# ProgramableResistor.net
KiCad netlist of a schematic drawn in Altium Designer
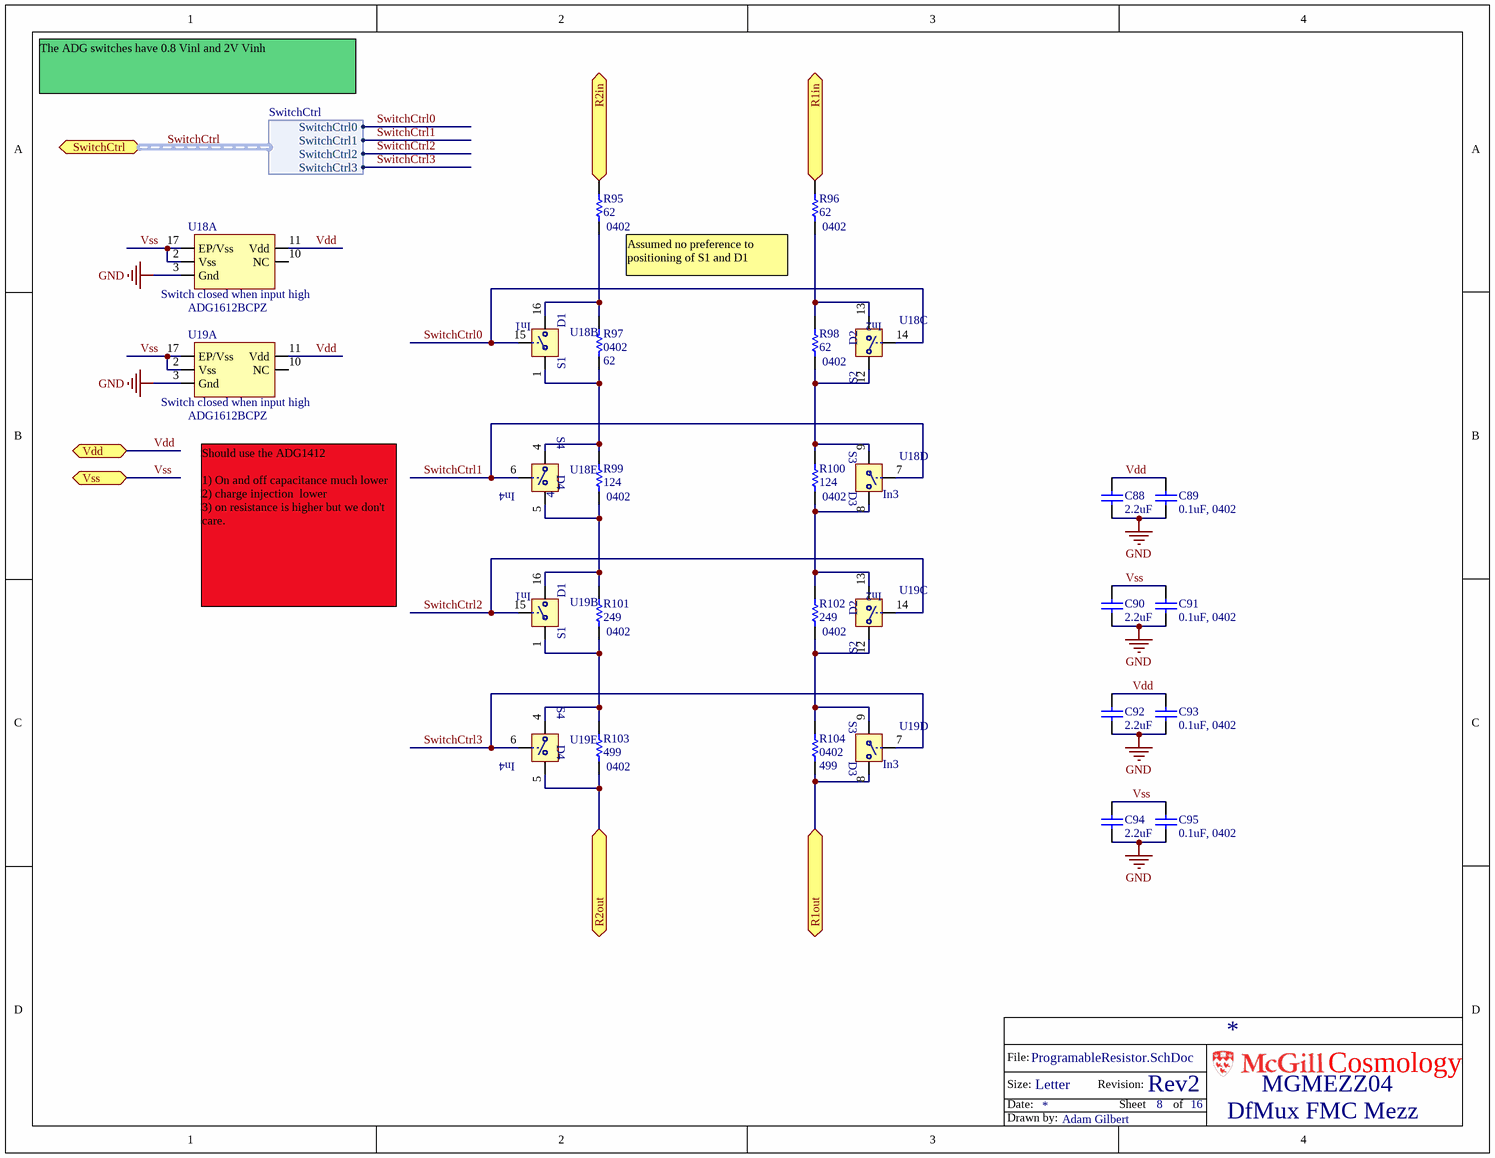
[diagram p0: ProgramableResistor.SchDoc]

(export (version "E")
  (design (tool "Eeschema 10.0.6"))
  (components
    (comp (ref "C88")
      (value "2.2uF")
      (footprint "0603")
      (description "Capacitor, Ceramic, 0603")
      (fields (field (name "MANUFACTURER") "TDK Corporation"))
      (libsource (lib "MGMEZZ04") (part "CAP 0603"))
    )
    (comp (ref "C89")
      (value "0.1uF, 0402")
      (footprint "0402")
      (description "Capacitor, Ceramic, 0402")
      (fields (field (name "MANUFACTURER") "TDK Corporation"))
      (libsource (lib "MGMEZZ04") (part "CAP 0603"))
    )
    (comp (ref "C90")
      (value "2.2uF")
      (footprint "0603")
      (description "Capacitor, Ceramic, 0603")
      (fields (field (name "MANUFACTURER") "TDK Corporation"))
      (libsource (lib "MGMEZZ04") (part "CAP 0603"))
    )
    (comp (ref "C91")
      (value "0.1uF, 0402")
      (footprint "0402")
      (description "Capacitor, Ceramic, 0402")
      (fields (field (name "MANUFACTURER") "TDK Corporation"))
      (libsource (lib "MGMEZZ04") (part "CAP 0603"))
    )
    (comp (ref "C92")
      (value "2.2uF")
      (footprint "0603")
      (description "Capacitor, Ceramic, 0603")
      (fields (field (name "MANUFACTURER") "TDK Corporation"))
      (libsource (lib "MGMEZZ04") (part "CAP 0603"))
    )
    (comp (ref "C93")
      (value "0.1uF, 0402")
      (footprint "0402")
      (description "Capacitor, Ceramic, 0402")
      (fields (field (name "MANUFACTURER") "TDK Corporation"))
      (libsource (lib "MGMEZZ04") (part "CAP 0603"))
    )
    (comp (ref "C94")
      (value "2.2uF")
      (footprint "0603")
      (description "Capacitor, Ceramic, 0603")
      (fields (field (name "MANUFACTURER") "TDK Corporation"))
      (libsource (lib "MGMEZZ04") (part "CAP 0603"))
    )
    (comp (ref "C95")
      (value "0.1uF, 0402")
      (footprint "0402")
      (description "Capacitor, Ceramic, 0402")
      (fields (field (name "MANUFACTURER") "TDK Corporation"))
      (libsource (lib "MGMEZZ04") (part "CAP 0603"))
    )
    (comp (ref "R95")
      (value "62")
      (footprint "0402")
      (description "Resistor")
      (fields (field (name "MANUFACTURER") "Generic"))
      (libsource (lib "MGMEZZ04") (part "RES 0402"))
    )
    (comp (ref "R96")
      (value "62")
      (footprint "0402")
      (description "Resistor")
      (fields (field (name "MANUFACTURER") "Generic"))
      (libsource (lib "MGMEZZ04") (part "RES 0402"))
    )
    (comp (ref "R97")
      (value "62")
      (footprint "0402")
      (description "Resistor")
      (fields (field (name "MANUFACTURER") "Generic"))
      (libsource (lib "MGMEZZ04") (part "RES 0402"))
    )
    (comp (ref "R98")
      (value "62")
      (footprint "0402")
      (description "Resistor")
      (fields (field (name "MANUFACTURER") "Generic"))
      (libsource (lib "MGMEZZ04") (part "RES 0402"))
    )
    (comp (ref "R99")
      (value "124")
      (footprint "0402")
      (description "Resistor")
      (fields (field (name "MANUFACTURER") "Generic"))
      (libsource (lib "MGMEZZ04") (part "RES 0402"))
    )
    (comp (ref "R100")
      (value "124")
      (footprint "0402")
      (description "Resistor")
      (fields (field (name "MANUFACTURER") "Generic"))
      (libsource (lib "MGMEZZ04") (part "RES 0402"))
    )
    (comp (ref "R101")
      (value "249")
      (footprint "0402")
      (description "Resistor")
      (fields (field (name "MANUFACTURER") "Generic"))
      (libsource (lib "MGMEZZ04") (part "RES 0402"))
    )
    (comp (ref "R102")
      (value "249")
      (footprint "0402")
      (description "Resistor")
      (fields (field (name "MANUFACTURER") "Generic"))
      (libsource (lib "MGMEZZ04") (part "RES 0402"))
    )
    (comp (ref "R103")
      (value "499")
      (footprint "0402")
      (description "Resistor")
      (fields (field (name "MANUFACTURER") "Generic"))
      (libsource (lib "MGMEZZ04") (part "RES 0402"))
    )
    (comp (ref "R104")
      (value "499")
      (footprint "0402")
      (description "Resistor")
      (fields (field (name "MANUFACTURER") "Generic"))
      (libsource (lib "MGMEZZ04") (part "RES 0402"))
    )
    (comp (ref "U18")
      (value "ADG1612BCPZ")
      (footprint "QFN127P600-8N")
      (description "Switch 4 SPST-NO - VQFN package")
      (fields (field (name "MANUFACTURER") "Analog Devices Inc"))
      (libsource (lib "") (part "ADG1612BCPZ_1"))
    )
    (comp (ref "U19")
      (value "ADG1612BCPZ")
      (footprint "QFN127P600-8N")
      (description "Switch 4 SPST-NO - VQFN package")
      (fields (field (name "MANUFACTURER") "Analog Devices Inc"))
      (libsource (lib "") (part "ADG1612BCPZ_1"))
    )
  )
  (nets
    (net (code "2") (name "/R1in") (class "Default")
      (node (ref "R96") (pin "2") (pinfunction "2_2") (pintype "passive"))
    )
    (net (code "3") (name "/R1out") (class "Default")
      (node (ref "R104") (pin "2") (pinfunction "2_2") (pintype "passive"))
      (node (ref "U19") (pin "8") (pinfunction "D3_8") (pintype "passive"))
    )
    (net (code "4") (name "/R2in") (class "Default")
      (node (ref "R95") (pin "2") (pinfunction "2_2") (pintype "passive"))
    )
    (net (code "5") (name "/R2out") (class "Default")
      (node (ref "R103") (pin "1") (pinfunction "1_1") (pintype "passive"))
      (node (ref "U19") (pin "5") (pinfunction "D4_5") (pintype "passive"))
    )
    (net (code "6") (name "/SwitchCtrl0") (class "Default")
      (node (ref "U18") (pin "14") (pinfunction "In2_14") (pintype "passive"))
      (node (ref "U18") (pin "15") (pinfunction "In1_15") (pintype "passive"))
    )
    (net (code "7") (name "/SwitchCtrl1") (class "Default")
      (node (ref "U18") (pin "6") (pinfunction "In4_6") (pintype "passive"))
      (node (ref "U18") (pin "7") (pinfunction "In3_7") (pintype "passive"))
    )
    (net (code "8") (name "/SwitchCtrl2") (class "Default")
      (node (ref "U19") (pin "14") (pinfunction "In2_14") (pintype "passive"))
      (node (ref "U19") (pin "15") (pinfunction "In1_15") (pintype "passive"))
    )
    (net (code "9") (name "/SwitchCtrl3") (class "Default")
      (node (ref "U19") (pin "6") (pinfunction "In4_6") (pintype "passive"))
      (node (ref "U19") (pin "7") (pinfunction "In3_7") (pintype "passive"))
    )
    (net (code "11") (name "/Vdd") (class "Default")
      (node (ref "C88") (pin "1") (pinfunction "1_1") (pintype "passive"))
      (node (ref "C89") (pin "2") (pinfunction "2_2") (pintype "passive"))
      (node (ref "C92") (pin "1") (pinfunction "1_1") (pintype "passive"))
      (node (ref "C93") (pin "2") (pinfunction "2_2") (pintype "passive"))
      (node (ref "U18") (pin "11") (pinfunction "Vdd_11") (pintype "passive"))
      (node (ref "U19") (pin "11") (pinfunction "Vdd_11") (pintype "passive"))
    )
    (net (code "12") (name "/Vss") (class "Default")
      (node (ref "C90") (pin "1") (pinfunction "1_1") (pintype "passive"))
      (node (ref "C91") (pin "2") (pinfunction "2_2") (pintype "passive"))
      (node (ref "C94") (pin "1") (pinfunction "1_1") (pintype "passive"))
      (node (ref "C95") (pin "2") (pinfunction "2_2") (pintype "passive"))
      (node (ref "U18") (pin "17") (pinfunction "EP/Vss_17") (pintype "passive"))
      (node (ref "U18") (pin "2") (pinfunction "Vss_2") (pintype "passive"))
      (node (ref "U19") (pin "17") (pinfunction "EP/Vss_17") (pintype "passive"))
      (node (ref "U19") (pin "2") (pinfunction "Vss_2") (pintype "passive"))
    )
    (net (code "13") (name "GND") (class "Default")
      (node (ref "C88") (pin "2") (pinfunction "2_2") (pintype "passive"))
      (node (ref "C89") (pin "1") (pinfunction "1_1") (pintype "passive"))
      (node (ref "C90") (pin "2") (pinfunction "2_2") (pintype "passive"))
      (node (ref "C91") (pin "1") (pinfunction "1_1") (pintype "passive"))
      (node (ref "C92") (pin "2") (pinfunction "2_2") (pintype "passive"))
      (node (ref "C93") (pin "1") (pinfunction "1_1") (pintype "passive"))
      (node (ref "C94") (pin "2") (pinfunction "2_2") (pintype "passive"))
      (node (ref "C95") (pin "1") (pinfunction "1_1") (pintype "passive"))
      (node (ref "U18") (pin "3") (pinfunction "Gnd_3") (pintype "passive"))
      (node (ref "U19") (pin "3") (pinfunction "Gnd_3") (pintype "passive"))
    )
    (net (code "14") (name "Net-(U18B-D1)") (class "Default")
      (node (ref "R95") (pin "1") (pinfunction "1_1") (pintype "passive"))
      (node (ref "R97") (pin "1") (pinfunction "1_1") (pintype "passive"))
      (node (ref "U18") (pin "16") (pinfunction "D1_16") (pintype "passive"))
    )
    (net (code "15") (name "Net-(U18B-S1)") (class "Default")
      (node (ref "R97") (pin "2") (pinfunction "2_2") (pintype "passive"))
      (node (ref "R99") (pin "2") (pinfunction "2_2") (pintype "passive"))
      (node (ref "U18") (pin "1") (pinfunction "S1_1") (pintype "passive"))
      (node (ref "U18") (pin "4") (pinfunction "S4_4") (pintype "passive"))
    )
    (net (code "16") (name "Net-(U18C-D2)") (class "Default")
      (node (ref "R96") (pin "1") (pinfunction "1_1") (pintype "passive"))
      (node (ref "R98") (pin "2") (pinfunction "2_2") (pintype "passive"))
      (node (ref "U18") (pin "13") (pinfunction "D2_13") (pintype "passive"))
    )
    (net (code "17") (name "Net-(U18C-S2)") (class "Default")
      (node (ref "R100") (pin "2") (pinfunction "2_2") (pintype "passive"))
      (node (ref "R98") (pin "1") (pinfunction "1_1") (pintype "passive"))
      (node (ref "U18") (pin "12") (pinfunction "S2_12") (pintype "passive"))
      (node (ref "U18") (pin "9") (pinfunction "S3_9") (pintype "passive"))
    )
    (net (code "18") (name "Net-(U18D-D3)") (class "Default")
      (node (ref "R100") (pin "1") (pinfunction "1_1") (pintype "passive"))
      (node (ref "R102") (pin "2") (pinfunction "2_2") (pintype "passive"))
      (node (ref "U18") (pin "8") (pinfunction "D3_8") (pintype "passive"))
      (node (ref "U19") (pin "13") (pinfunction "D2_13") (pintype "passive"))
    )
    (net (code "19") (name "Net-(U18E-D4)") (class "Default")
      (node (ref "R101") (pin "2") (pinfunction "2_2") (pintype "passive"))
      (node (ref "R99") (pin "1") (pinfunction "1_1") (pintype "passive"))
      (node (ref "U18") (pin "5") (pinfunction "D4_5") (pintype "passive"))
      (node (ref "U19") (pin "16") (pinfunction "D1_16") (pintype "passive"))
    )
    (net (code "20") (name "Net-(U19B-S1)") (class "Default")
      (node (ref "R101") (pin "1") (pinfunction "1_1") (pintype "passive"))
      (node (ref "R103") (pin "2") (pinfunction "2_2") (pintype "passive"))
      (node (ref "U19") (pin "1") (pinfunction "S1_1") (pintype "passive"))
      (node (ref "U19") (pin "4") (pinfunction "S4_4") (pintype "passive"))
    )
    (net (code "21") (name "Net-(U19C-S2)") (class "Default")
      (node (ref "R102") (pin "1") (pinfunction "1_1") (pintype "passive"))
      (node (ref "R104") (pin "1") (pinfunction "1_1") (pintype "passive"))
      (node (ref "U19") (pin "12") (pinfunction "S2_12") (pintype "passive"))
      (node (ref "U19") (pin "9") (pinfunction "S3_9") (pintype "passive"))
    )
    (net (code "22") (name "unconnected-(U18A-NC-Pad10)") (class "Default")
      (node (ref "U18") (pin "10") (pinfunction "NC_10") (pintype "passive"))
    )
    (net (code "23") (name "unconnected-(U19A-NC-Pad10)") (class "Default")
      (node (ref "U19") (pin "10") (pinfunction "NC_10") (pintype "passive"))
    )
  )
)
